# main-unit-psu.net
KiCad netlist of a schematic drawn in EAGLE
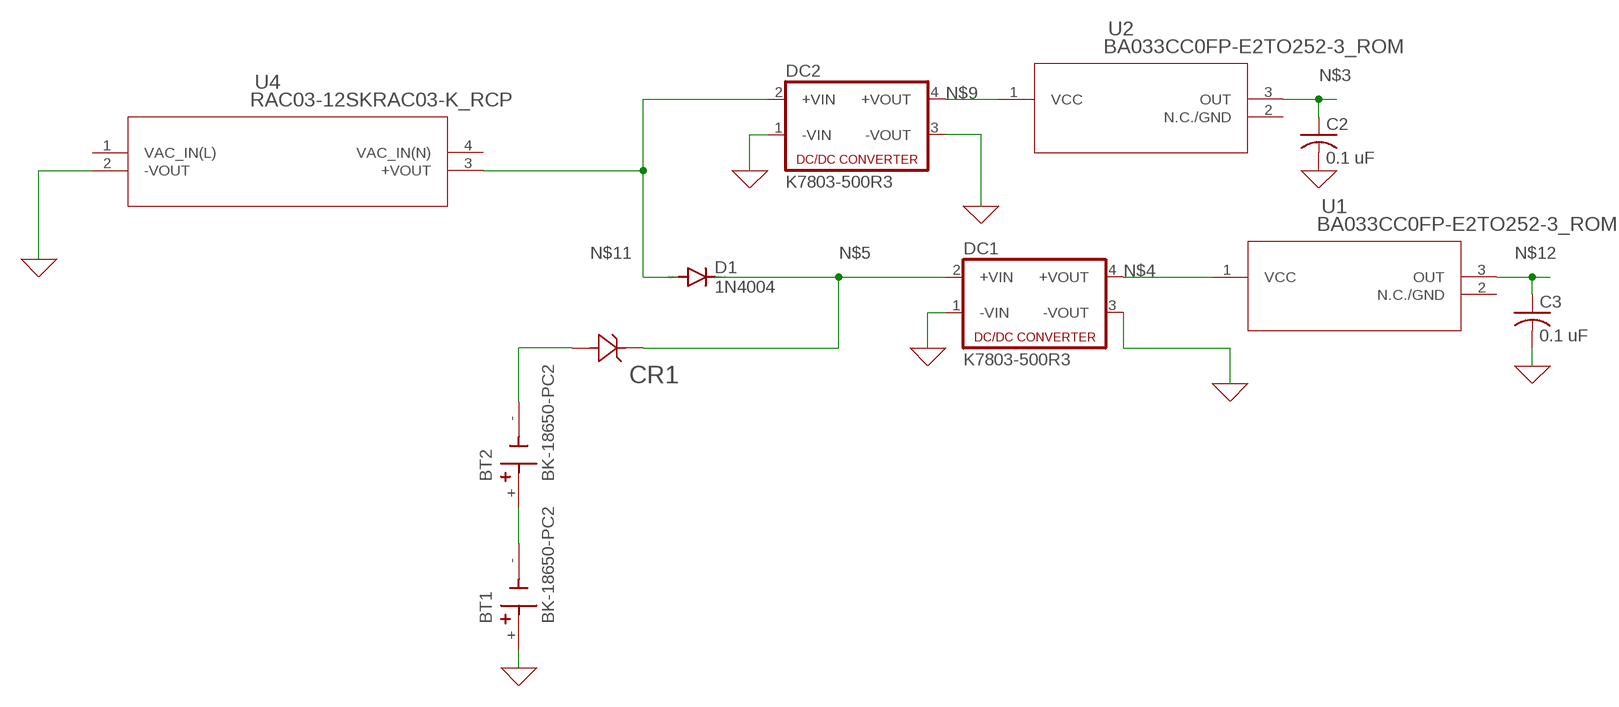
[diagram p0: schematic, sheet 1]

(export (version "E")
  (design (tool "Eeschema 10.0.6"))
  (components
    (comp (ref "BT1")
      (value "BK-18650-PC2")
      (footprint "eagle-import:BAT_BK-18650-PC2")
      (fields (field (name "MF") "MPD (Memory Protection Devices)"))
      (libsource (lib "eagle-import") (part "BK-18650-PC2"))
    )
    (comp (ref "BT2")
      (value "BK-18650-PC2")
      (footprint "eagle-import:BAT_BK-18650-PC2")
      (fields (field (name "MF") "MPD (Memory Protection Devices)"))
      (libsource (lib "eagle-import") (part "BK-18650-PC2"))
    )
    (comp (ref "C2")
      (value "0.1 uF")
      (footprint "eagle-import:C050-024X044")
      (libsource (lib "eagle-import") (part "C-US050-024X044"))
    )
    (comp (ref "C3")
      (value "0.1 uF")
      (footprint "eagle-import:C050-024X044")
      (libsource (lib "eagle-import") (part "C-US050-024X044"))
    )
    (comp (ref "CR1")
      (value "1N5819DO-41_STM")
      (footprint "eagle-import:DO-41_STM")
      (fields
        (field (name "MANUFACTURER_PART_NUMBER") "1N5819")
        (field (name "COPYRIGHT") "Copyright (C) 2023 Ultra Librarian. All rights reserved.")
      )
      (libsource (lib "eagle-import") (part "1N5819DO-41_STM"))
    )
    (comp (ref "D1")
      (value "1N4004")
      (footprint "eagle-import:DO41-10")
      (libsource (lib "eagle-import") (part "1N4004"))
    )
    (comp (ref "DC1")
      (value "K7803-500R3")
      (footprint "eagle-import:NME")
      (fields (field (name "MF") "C & D TECHNOLOGIES, INC") (field (name "MPN") "NME1205D"))
      (libsource (lib "eagle-import") (part "NME"))
    )
    (comp (ref "DC2")
      (value "K7803-500R3")
      (footprint "eagle-import:NME")
      (fields (field (name "MF") "C & D TECHNOLOGIES, INC") (field (name "MPN") "NME1205D"))
      (libsource (lib "eagle-import") (part "NME"))
    )
    (comp (ref "U1")
      (value "BA033CC0FP-E2TO252-3_ROM")
      (footprint "eagle-import:TO252-3_ROM")
      (fields
        (field (name "MANUFACTURER_PART_NUMBER") "BA033CC0FP-E2")
        (field (name "COPYRIGHT") "Copyright (C) 2023 Ultra Librarian. All rights reserved.")
      )
      (libsource (lib "eagle-import") (part "BA033CC0FP-E2TO252-3_ROM"))
    )
    (comp (ref "U2")
      (value "BA033CC0FP-E2TO252-3_ROM")
      (footprint "eagle-import:TO252-3_ROM")
      (fields
        (field (name "MANUFACTURER_PART_NUMBER") "BA033CC0FP-E2")
        (field (name "COPYRIGHT") "Copyright (C) 2023 Ultra Librarian. All rights reserved.")
      )
      (libsource (lib "eagle-import") (part "BA033CC0FP-E2TO252-3_ROM"))
    )
    (comp (ref "U4")
      (value "RAC03-12SKRAC03-K_RCP")
      (footprint "eagle-import:RAC03-K_RCP")
      (fields
        (field (name "MANUFACTURER_PART_NUMBER") "RAC03-12SK")
        (field (name "COPYRIGHT") "Copyright (C) 2023 Ultra Librarian. All rights reserved.")
      )
      (libsource (lib "eagle-import") (part "RAC03-12SKRAC03-K_RCP"))
    )
  )
  (nets
    (net (code "1") (name "/N$3") (class "Default")
      (node (ref "C2") (pin "1") (pinfunction "1_1") (pintype "passive"))
      (node (ref "U2") (pin "3") (pinfunction "OUT_3") (pintype "output"))
    )
    (net (code "2") (name "/N$4") (class "Default")
      (node (ref "DC1") (pin "4") (pinfunction "+VOUT_4") (pintype "passive"))
      (node (ref "U1") (pin "1") (pinfunction "VCC_1") (pintype "power_in"))
    )
    (net (code "3") (name "/N$5") (class "Default")
      (node (ref "CR1") (pin "1") (pinfunction "1_1") (pintype "passive"))
      (node (ref "D1") (pin "C") (pinfunction "C_C") (pintype "passive"))
      (node (ref "DC1") (pin "2") (pinfunction "+VIN_2") (pintype "passive"))
    )
    (net (code "4") (name "/N$9") (class "Default")
      (node (ref "DC2") (pin "4") (pinfunction "+VOUT_4") (pintype "passive"))
      (node (ref "U2") (pin "1") (pinfunction "VCC_1") (pintype "power_in"))
    )
    (net (code "5") (name "/N$11") (class "Default")
      (node (ref "D1") (pin "A") (pinfunction "A_A") (pintype "passive"))
      (node (ref "DC2") (pin "2") (pinfunction "+VIN_2") (pintype "passive"))
      (node (ref "U4") (pin "3") (pinfunction "+VOUT_3") (pintype "output"))
    )
    (net (code "6") (name "/N$12") (class "Default")
      (node (ref "C3") (pin "1") (pinfunction "1_1") (pintype "passive"))
      (node (ref "U1") (pin "3") (pinfunction "OUT_3") (pintype "output"))
    )
    (net (code "7") (name "/VAC_IN(L)") (class "Default")
      (node (ref "U4") (pin "1") (pinfunction "VAC_IN(L)_1") (pintype "power_in"))
    )
    (net (code "8") (name "/VAC_IN(N)") (class "Default")
      (node (ref "U4") (pin "4") (pinfunction "VAC_IN(N)_4") (pintype "power_in"))
    )
    (net (code "9") (name "GND") (class "Default")
      (node (ref "BT1") (pin "+") (pinfunction "+_+") (pintype "passive"))
      (node (ref "C2") (pin "2") (pinfunction "2_2") (pintype "passive"))
      (node (ref "C3") (pin "2") (pinfunction "2_2") (pintype "passive"))
      (node (ref "DC1") (pin "1") (pinfunction "-VIN_1") (pintype "passive"))
      (node (ref "DC1") (pin "3") (pinfunction "-VOUT_3") (pintype "passive"))
      (node (ref "DC2") (pin "1") (pinfunction "-VIN_1") (pintype "passive"))
      (node (ref "DC2") (pin "3") (pinfunction "-VOUT_3") (pintype "passive"))
      (node (ref "U4") (pin "2") (pinfunction "-VOUT_2") (pintype "output"))
    )
    (net (code "10") (name "Net-(BT1-Pad-)") (class "Default")
      (node (ref "BT1") (pin "-") (pinfunction "-_-") (pintype "passive"))
      (node (ref "BT2") (pin "+") (pinfunction "+_+") (pintype "passive"))
    )
    (net (code "11") (name "Net-(BT2-Pad-)") (class "Default")
      (node (ref "BT2") (pin "-") (pinfunction "-_-") (pintype "passive"))
      (node (ref "CR1") (pin "2") (pinfunction "2_2") (pintype "passive"))
    )
    (net (code "12") (name "unconnected-(U1-N.C.{slash}GND-Pad2)") (class "Default")
      (node (ref "U1") (pin "2") (pinfunction "N.C./GND_2") (pintype "no_connect"))
    )
    (net (code "13") (name "unconnected-(U2-N.C.{slash}GND-Pad2)") (class "Default")
      (node (ref "U2") (pin "2") (pinfunction "N.C./GND_2") (pintype "no_connect"))
    )
  )
)
